# kitt.net
KiCad netlist of a schematic drawn in EAGLE
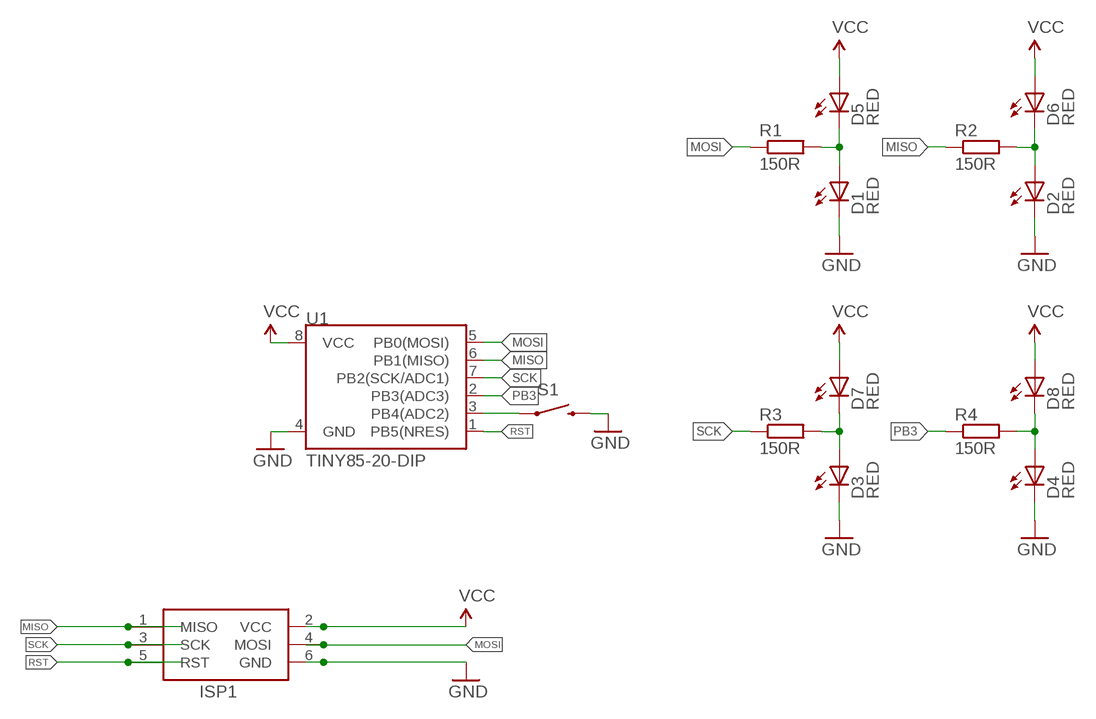
[diagram p0: schematic, sheet 1]

(export (version "E")
  (design (tool "Eeschema 10.0.6"))
  (components
    (comp (ref "D1")
      (value "RED")
      (footprint "eagle-import:CHIP-LED0805")
      (libsource (lib "eagle-import") (part "LEDCHIP-LED0805"))
    )
    (comp (ref "D2")
      (value "RED")
      (footprint "eagle-import:CHIP-LED0805")
      (libsource (lib "eagle-import") (part "LEDCHIP-LED0805"))
    )
    (comp (ref "D3")
      (value "RED")
      (footprint "eagle-import:CHIP-LED0805")
      (libsource (lib "eagle-import") (part "LEDCHIP-LED0805"))
    )
    (comp (ref "D4")
      (value "RED")
      (footprint "eagle-import:CHIP-LED0805")
      (libsource (lib "eagle-import") (part "LEDCHIP-LED0805"))
    )
    (comp (ref "D5")
      (value "RED")
      (footprint "eagle-import:CHIP-LED0805")
      (libsource (lib "eagle-import") (part "LEDCHIP-LED0805"))
    )
    (comp (ref "D6")
      (value "RED")
      (footprint "eagle-import:CHIP-LED0805")
      (libsource (lib "eagle-import") (part "LEDCHIP-LED0805"))
    )
    (comp (ref "D7")
      (value "RED")
      (footprint "eagle-import:CHIP-LED0805")
      (libsource (lib "eagle-import") (part "LEDCHIP-LED0805"))
    )
    (comp (ref "D8")
      (value "RED")
      (footprint "eagle-import:CHIP-LED0805")
      (libsource (lib "eagle-import") (part "LEDCHIP-LED0805"))
    )
    (comp (ref "ISP1")
      (value "AVRISP-BOX")
      (footprint "eagle-import:AVRISP-BOX")
      (libsource (lib "eagle-import") (part "AVRISP-BOX"))
    )
    (comp (ref "R1")
      (value "150R")
      (footprint "eagle-import:M0805")
      (libsource (lib "eagle-import") (part "R-EU_M0805"))
    )
    (comp (ref "R2")
      (value "150R")
      (footprint "eagle-import:M0805")
      (libsource (lib "eagle-import") (part "R-EU_M0805"))
    )
    (comp (ref "R3")
      (value "150R")
      (footprint "eagle-import:M0805")
      (libsource (lib "eagle-import") (part "R-EU_M0805"))
    )
    (comp (ref "R4")
      (value "150R")
      (footprint "eagle-import:M0805")
      (libsource (lib "eagle-import") (part "R-EU_M0805"))
    )
    (comp (ref "S1")
      (value "SWITCH-MOMENTARY-2PTH")
      (footprint "eagle-import:TACTILE-PTH")
      (libsource (lib "eagle-import") (part "SWITCH-MOMENTARY-2PTH"))
    )
    (comp (ref "U1")
      (value "TINY85-20-DIP")
      (footprint "eagle-import:DIP08")
      (libsource (lib "eagle-import") (part "ATTINY45TINY85-20-DIP"))
    )
  )
  (nets
    (net (code "1") (name "GND") (class "Default")
      (node (ref "D1") (pin "C") (pinfunction "C_C") (pintype "passive"))
      (node (ref "D2") (pin "C") (pinfunction "C_C") (pintype "passive"))
      (node (ref "D3") (pin "C") (pinfunction "C_C") (pintype "passive"))
      (node (ref "D4") (pin "C") (pinfunction "C_C") (pintype "passive"))
      (node (ref "ISP1") (pin "6") (pinfunction "GND_6") (pintype "power_in"))
      (node (ref "S1") (pin "3") (pinfunction "2_3") (pintype "passive"))
      (node (ref "U1") (pin "4") (pinfunction "GND_4") (pintype "bidirectional"))
    )
    (net (code "2") (name "MISO") (class "Default")
      (node (ref "ISP1") (pin "1") (pinfunction "MISO_1") (pintype "input"))
      (node (ref "R2") (pin "1") (pinfunction "1_1") (pintype "passive"))
      (node (ref "U1") (pin "6") (pinfunction "PB1(MISO)_6") (pintype "bidirectional"))
    )
    (net (code "3") (name "MOSI") (class "Default")
      (node (ref "ISP1") (pin "4") (pinfunction "MOSI_4") (pintype "output"))
      (node (ref "R1") (pin "1") (pinfunction "1_1") (pintype "passive"))
      (node (ref "U1") (pin "5") (pinfunction "PB0(MOSI)_5") (pintype "bidirectional"))
    )
    (net (code "4") (name "Net-(D1-PadA)") (class "Default")
      (node (ref "D1") (pin "A") (pinfunction "A_A") (pintype "passive"))
      (node (ref "D5") (pin "C") (pinfunction "C_C") (pintype "passive"))
      (node (ref "R1") (pin "2") (pinfunction "2_2") (pintype "passive"))
    )
    (net (code "5") (name "Net-(D2-PadA)") (class "Default")
      (node (ref "D2") (pin "A") (pinfunction "A_A") (pintype "passive"))
      (node (ref "D6") (pin "C") (pinfunction "C_C") (pintype "passive"))
      (node (ref "R2") (pin "2") (pinfunction "2_2") (pintype "passive"))
    )
    (net (code "6") (name "Net-(D3-PadA)") (class "Default")
      (node (ref "D3") (pin "A") (pinfunction "A_A") (pintype "passive"))
      (node (ref "D7") (pin "C") (pinfunction "C_C") (pintype "passive"))
      (node (ref "R3") (pin "2") (pinfunction "2_2") (pintype "passive"))
    )
    (net (code "7") (name "Net-(D4-PadA)") (class "Default")
      (node (ref "D4") (pin "A") (pinfunction "A_A") (pintype "passive"))
      (node (ref "D8") (pin "C") (pinfunction "C_C") (pintype "passive"))
      (node (ref "R4") (pin "2") (pinfunction "2_2") (pintype "passive"))
    )
    (net (code "8") (name "Net-(U1-PB4(ADC2))") (class "Default")
      (node (ref "S1") (pin "1") (pinfunction "1_1") (pintype "passive"))
      (node (ref "U1") (pin "3") (pinfunction "PB4(ADC2)_3") (pintype "bidirectional"))
    )
    (net (code "9") (name "PB3") (class "Default")
      (node (ref "R4") (pin "1") (pinfunction "1_1") (pintype "passive"))
      (node (ref "U1") (pin "2") (pinfunction "PB3(ADC3)_2") (pintype "bidirectional"))
    )
    (net (code "10") (name "RST") (class "Default")
      (node (ref "ISP1") (pin "5") (pinfunction "RST_5") (pintype "output"))
      (node (ref "U1") (pin "1") (pinfunction "PB5(NRES)_1") (pintype "bidirectional"))
    )
    (net (code "11") (name "SCK") (class "Default")
      (node (ref "ISP1") (pin "3") (pinfunction "SCK_3") (pintype "output"))
      (node (ref "R3") (pin "1") (pinfunction "1_1") (pintype "passive"))
      (node (ref "U1") (pin "7") (pinfunction "PB2(SCK/ADC1)_7") (pintype "bidirectional"))
    )
    (net (code "12") (name "VCC") (class "Default")
      (node (ref "D5") (pin "A") (pinfunction "A_A") (pintype "passive"))
      (node (ref "D6") (pin "A") (pinfunction "A_A") (pintype "passive"))
      (node (ref "D7") (pin "A") (pinfunction "A_A") (pintype "passive"))
      (node (ref "D8") (pin "A") (pinfunction "A_A") (pintype "passive"))
      (node (ref "ISP1") (pin "2") (pinfunction "VCC_2") (pintype "power_in"))
      (node (ref "U1") (pin "8") (pinfunction "VCC_8") (pintype "bidirectional"))
    )
  )
)
